# GigabitEthernet_VSC8211.net
KiCad netlist of a schematic drawn in Altium Designer
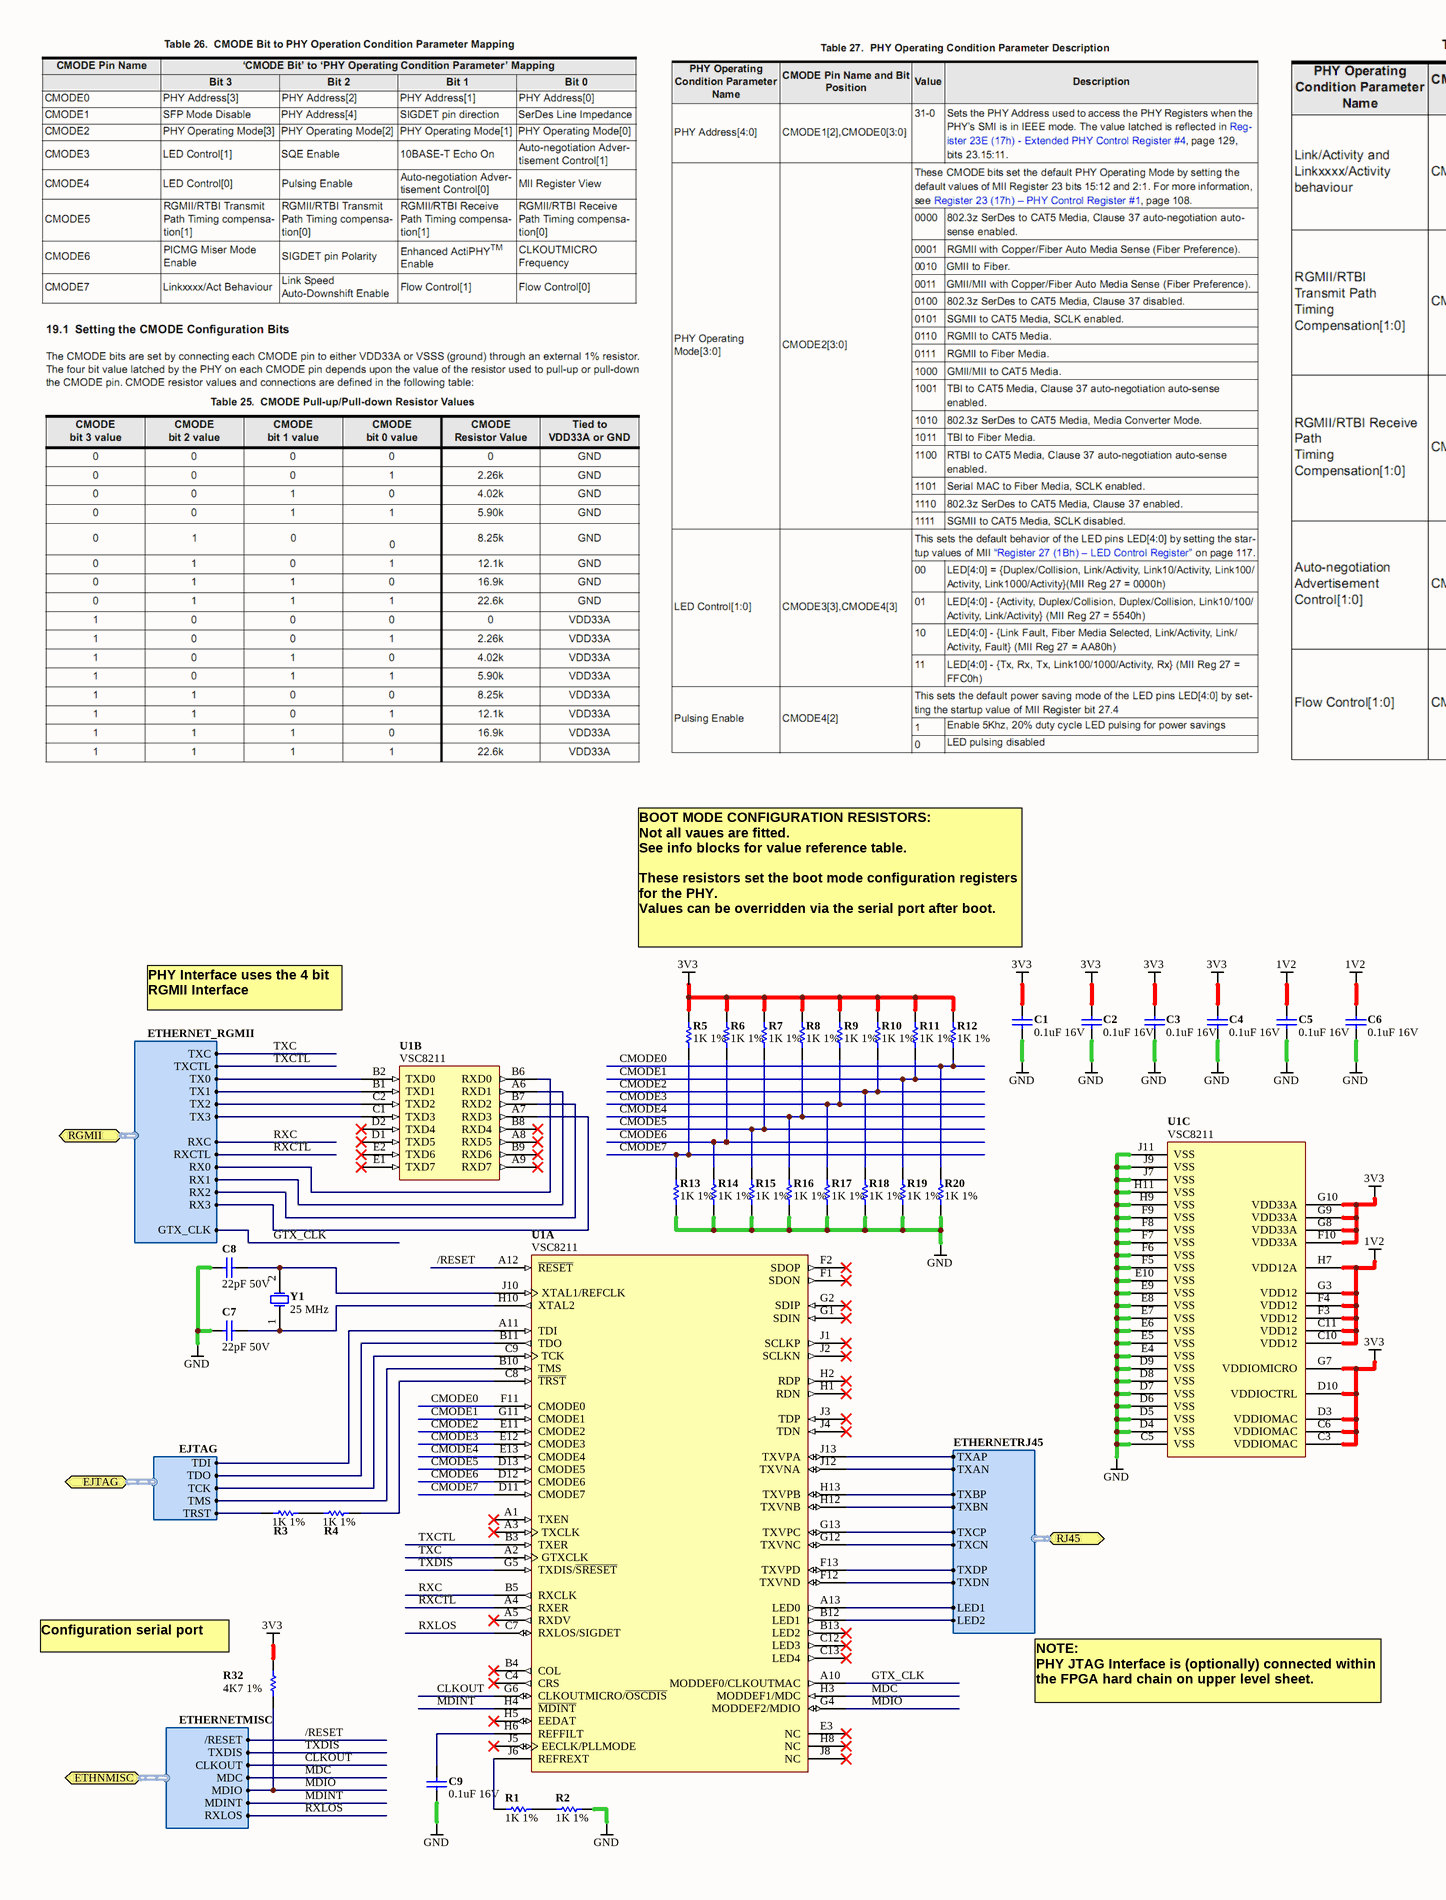
[diagram p0: GigabitEthernet_VSC8211.SchDoc, left]
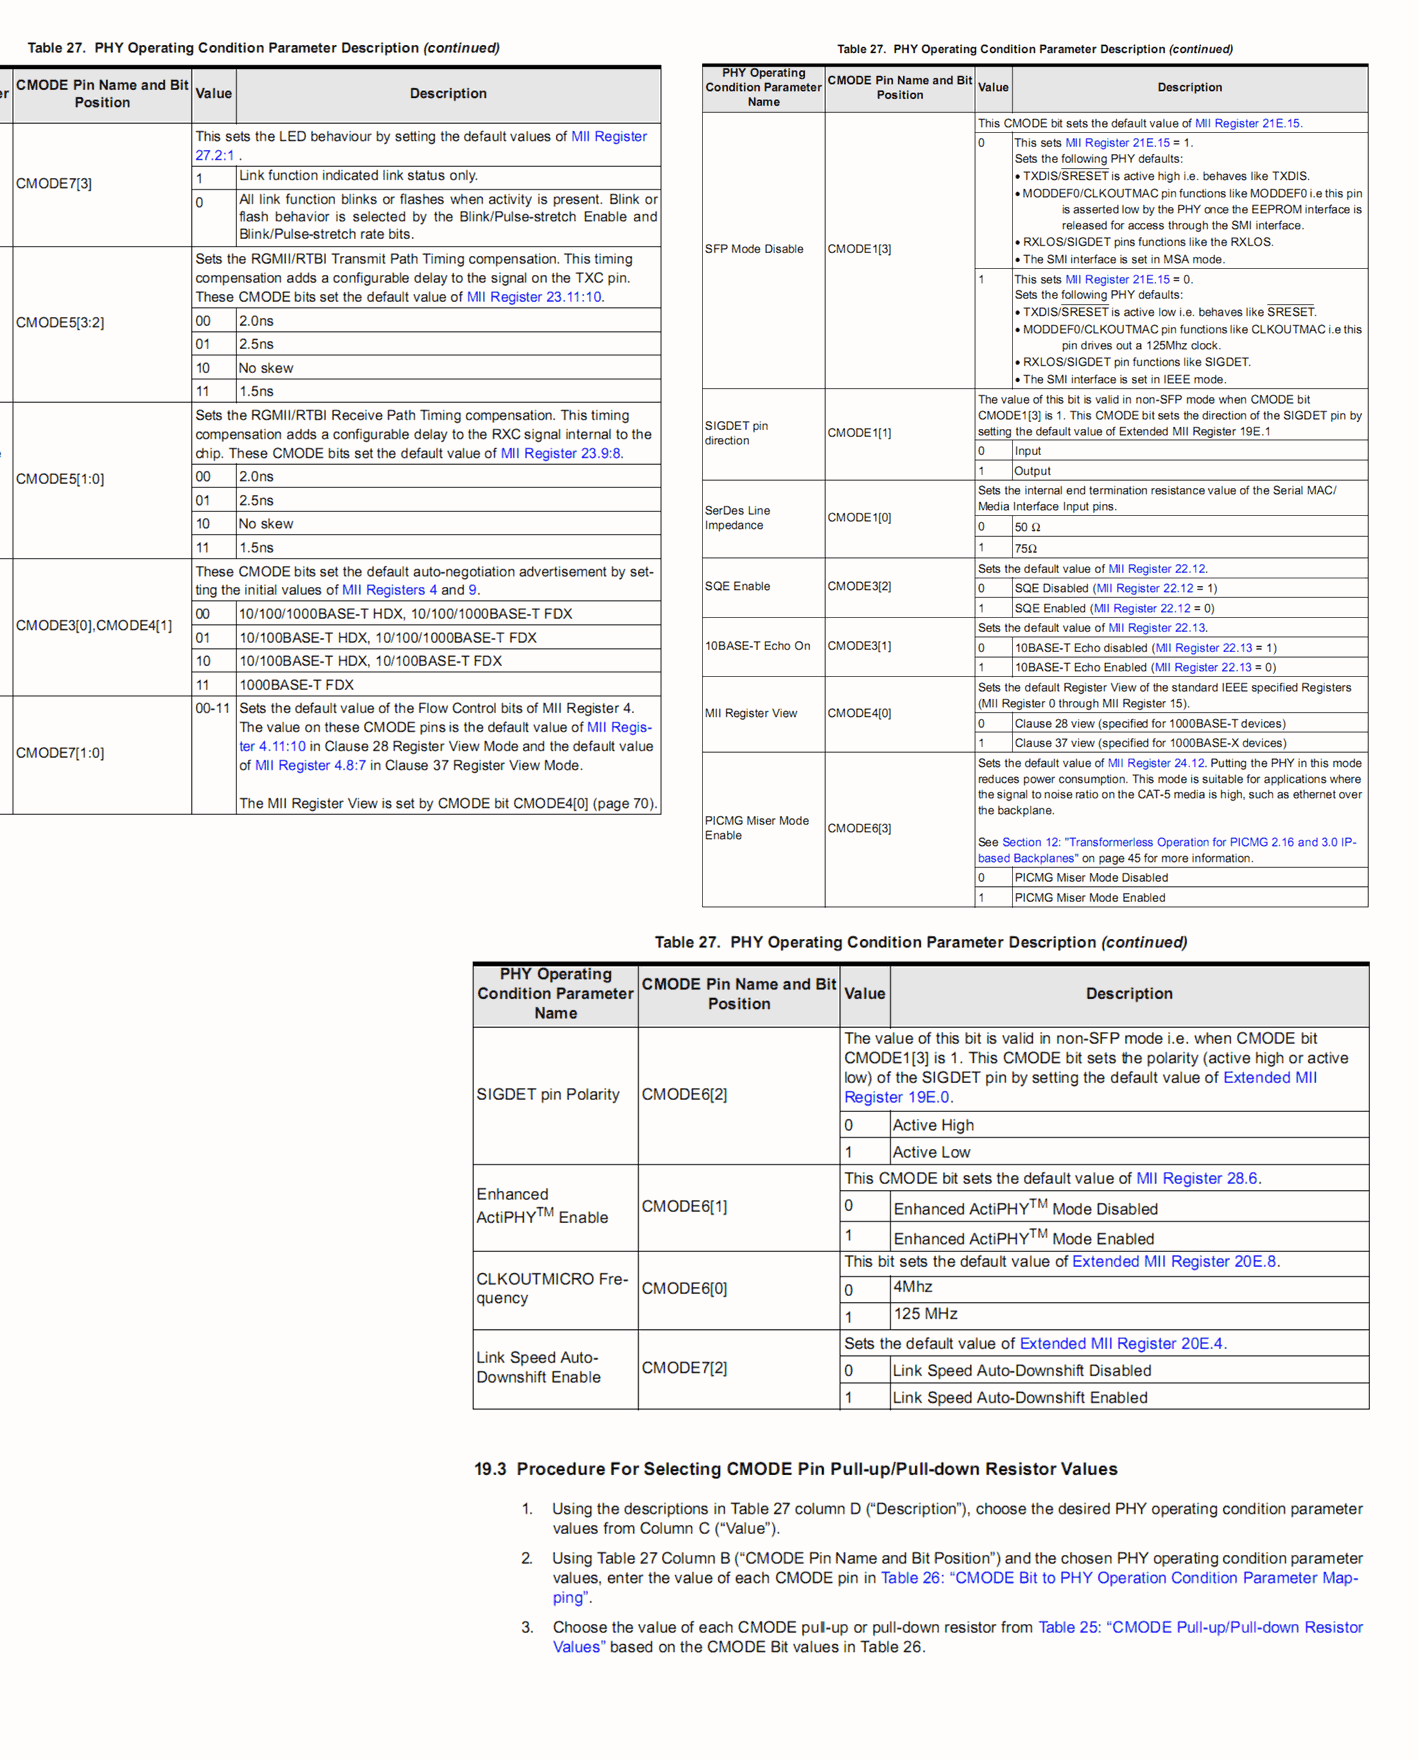
[diagram p1: GigabitEthernet_VSC8211.SchDoc, right]

(export (version "E")
  (design (tool "Eeschema 10.0.6"))
  (components
    (comp (ref "C1")
      (value "0.1uF 16V")
      (footprint "CAPC1005-STAR")
      (description "Capacitor, Ceramic, 0.1uF 10% 16V 0402 (1005) X7R")
      (fields (field (name "TOLERANCE") "10 %"))
      (libsource (lib "altium-import") (part "root_0_mirrored_CAP-NP_"))
    )
    (comp (ref "C2")
      (value "0.1uF 16V")
      (footprint "CAPC1005-STAR")
      (description "Capacitor, Ceramic, 0.1uF 10% 16V 0402 (1005) X7R")
      (fields (field (name "TOLERANCE") "10 %"))
      (libsource (lib "altium-import") (part "root_0_mirrored_CAP-NP_"))
    )
    (comp (ref "C3")
      (value "0.1uF 16V")
      (footprint "CAPC1005-STAR")
      (description "Capacitor, Ceramic, 0.1uF 10% 16V 0402 (1005) X7R")
      (fields (field (name "TOLERANCE") "10 %"))
      (libsource (lib "altium-import") (part "root_0_mirrored_CAP-NP_"))
    )
    (comp (ref "C4")
      (value "0.1uF 16V")
      (footprint "CAPC1005-STAR")
      (description "Capacitor, Ceramic, 0.1uF 10% 16V 0402 (1005) X7R")
      (fields (field (name "TOLERANCE") "10 %"))
      (libsource (lib "altium-import") (part "root_0_mirrored_CAP-NP_"))
    )
    (comp (ref "C5")
      (value "0.1uF 16V")
      (footprint "CAPC1005-STAR")
      (description "Capacitor, Ceramic, 0.1uF 10% 16V 0402 (1005) X7R")
      (fields (field (name "TOLERANCE") "10 %"))
      (libsource (lib "altium-import") (part "root_0_mirrored_CAP-NP_"))
    )
    (comp (ref "C6")
      (value "0.1uF 16V")
      (footprint "CAPC1005-STAR")
      (description "Capacitor, Ceramic, 0.1uF 10% 16V 0402 (1005) X7R")
      (fields (field (name "TOLERANCE") "10 %"))
      (libsource (lib "altium-import") (part "root_0_mirrored_CAP-NP_"))
    )
    (comp (ref "C7")
      (value "22pF 50V")
      (footprint "CAPC1005-STAR")
      (description "Capacitor, Ceramic, 22pF 5% 50V 0402 (1005) COG")
      (fields (field (name "TOLERANCE") "5 %"))
      (libsource (lib "AltiumDesignLibrary") (part "CAP-NP"))
    )
    (comp (ref "C8")
      (value "22pF 50V")
      (footprint "CAPC1005-STAR")
      (description "Capacitor, Ceramic, 22pF 5% 50V 0402 (1005) COG")
      (fields (field (name "TOLERANCE") "5 %"))
      (libsource (lib "AltiumDesignLibrary") (part "CAP-NP"))
    )
    (comp (ref "C9")
      (value "0.1uF 16V")
      (footprint "CAPC1005-STAR")
      (description "Capacitor, Ceramic, 0.1uF 10% 16V 0402 (1005) X7R")
      (fields (field (name "TOLERANCE") "10 %"))
      (libsource (lib "altium-import") (part "root_0_CAP-NP_"))
    )
    (comp (ref "R1")
      (value "1K 1%")
      (footprint "RESC1005-STAR")
      (description "Resistor, 1K 1% 0402 (1005)")
      (fields (field (name "TOLERANCE") "1 %"))
      (libsource (lib "AltiumDesignLibrary") (part "RES"))
    )
    (comp (ref "R2")
      (value "1K 1%")
      (footprint "RESC1005-STAR")
      (description "Resistor, 1K 1% 0402 (1005)")
      (fields (field (name "TOLERANCE") "1 %"))
      (libsource (lib "AltiumDesignLibrary") (part "RES"))
    )
    (comp (ref "R3")
      (value "1K 1%")
      (footprint "RESC1005-STAR")
      (description "Resistor, 1K 1% 0402 (1005)")
      (fields (field (name "TOLERANCE") "1 %"))
      (libsource (lib "AltiumDesignLibrary") (part "RES"))
    )
    (comp (ref "R4")
      (value "1K 1%")
      (footprint "RESC1005-STAR")
      (description "Resistor, 1K 1% 0402 (1005)")
      (fields (field (name "TOLERANCE") "1 %"))
      (libsource (lib "AltiumDesignLibrary") (part "RES"))
    )
    (comp (ref "R5")
      (value "1K 1%")
      (footprint "RESC1005-STAR")
      (description "Resistor, 1K 1% 0402 (1005)")
      (fields (field (name "TOLERANCE") "1 %"))
      (libsource (lib "AltiumDesignLibrary") (part "RES"))
    )
    (comp (ref "R6")
      (value "1K 1%")
      (footprint "RESC1005-STAR")
      (description "Resistor, 1K 1% 0402 (1005)")
      (fields (field (name "TOLERANCE") "1 %"))
      (libsource (lib "AltiumDesignLibrary") (part "RES"))
    )
    (comp (ref "R7")
      (value "1K 1%")
      (footprint "RESC1005-STAR")
      (description "Resistor, 1K 1% 0402 (1005)")
      (fields (field (name "TOLERANCE") "1 %"))
      (libsource (lib "AltiumDesignLibrary") (part "RES"))
    )
    (comp (ref "R8")
      (value "1K 1%")
      (footprint "RESC1005-STAR")
      (description "Resistor, 1K 1% 0402 (1005)")
      (fields (field (name "TOLERANCE") "1 %"))
      (libsource (lib "AltiumDesignLibrary") (part "RES"))
    )
    (comp (ref "R9")
      (value "1K 1%")
      (footprint "RESC1005-STAR")
      (description "Resistor, 1K 1% 0402 (1005)")
      (fields (field (name "TOLERANCE") "1 %"))
      (libsource (lib "AltiumDesignLibrary") (part "RES"))
    )
    (comp (ref "R10")
      (value "1K 1%")
      (footprint "RESC1005-STAR")
      (description "Resistor, 1K 1% 0402 (1005)")
      (fields (field (name "TOLERANCE") "1 %"))
      (libsource (lib "AltiumDesignLibrary") (part "RES"))
    )
    (comp (ref "R11")
      (value "1K 1%")
      (footprint "RESC1005-STAR")
      (description "Resistor, 1K 1% 0402 (1005)")
      (fields (field (name "TOLERANCE") "1 %"))
      (libsource (lib "AltiumDesignLibrary") (part "RES"))
    )
    (comp (ref "R12")
      (value "1K 1%")
      (footprint "RESC1005-STAR")
      (description "Resistor, 1K 1% 0402 (1005)")
      (fields (field (name "TOLERANCE") "1 %"))
      (libsource (lib "AltiumDesignLibrary") (part "RES"))
    )
    (comp (ref "R13")
      (value "1K 1%")
      (footprint "RESC1005-STAR")
      (description "Resistor, 1K 1% 0402 (1005)")
      (fields (field (name "TOLERANCE") "1 %"))
      (libsource (lib "AltiumDesignLibrary") (part "RES"))
    )
    (comp (ref "R14")
      (value "1K 1%")
      (footprint "RESC1005-STAR")
      (description "Resistor, 1K 1% 0402 (1005)")
      (fields (field (name "TOLERANCE") "1 %"))
      (libsource (lib "AltiumDesignLibrary") (part "RES"))
    )
    (comp (ref "R15")
      (value "1K 1%")
      (footprint "RESC1005-STAR")
      (description "Resistor, 1K 1% 0402 (1005)")
      (fields (field (name "TOLERANCE") "1 %"))
      (libsource (lib "AltiumDesignLibrary") (part "RES"))
    )
    (comp (ref "R16")
      (value "1K 1%")
      (footprint "RESC1005-STAR")
      (description "Resistor, 1K 1% 0402 (1005)")
      (fields (field (name "TOLERANCE") "1 %"))
      (libsource (lib "AltiumDesignLibrary") (part "RES"))
    )
    (comp (ref "R17")
      (value "1K 1%")
      (footprint "RESC1005-STAR")
      (description "Resistor, 1K 1% 0402 (1005)")
      (fields (field (name "TOLERANCE") "1 %"))
      (libsource (lib "AltiumDesignLibrary") (part "RES"))
    )
    (comp (ref "R18")
      (value "1K 1%")
      (footprint "RESC1005-STAR")
      (description "Resistor, 1K 1% 0402 (1005)")
      (fields (field (name "TOLERANCE") "1 %"))
      (libsource (lib "AltiumDesignLibrary") (part "RES"))
    )
    (comp (ref "R19")
      (value "1K 1%")
      (footprint "RESC1005-STAR")
      (description "Resistor, 1K 1% 0402 (1005)")
      (fields (field (name "TOLERANCE") "1 %"))
      (libsource (lib "AltiumDesignLibrary") (part "RES"))
    )
    (comp (ref "R20")
      (value "1K 1%")
      (footprint "RESC1005-STAR")
      (description "Resistor, 1K 1% 0402 (1005)")
      (fields (field (name "TOLERANCE") "1 %"))
      (libsource (lib "AltiumDesignLibrary") (part "RES"))
    )
    (comp (ref "R32")
      (value "4K7 1%")
      (footprint "RESC1005-STAR")
      (description "Resistor, 4K7 1% 0402 (1005)")
      (fields (field (name "TOLERANCE") "1 %"))
      (libsource (lib "AltiumDesignLibrary") (part "RES"))
    )
    (comp (ref "U1")
      (value "VSC8211")
      (footprint "BGA117C100P9X13_1000X1400X170")
      (description "Ethernet PHY, Gigabit, Vitesse, VSC8211")
      (libsource (lib "AltiumDesignLibrary") (part "VSC8211XVW"))
    )
    (comp (ref "Y1")
      (value "25 MHz")
      (footprint "XTAL_HC49SMD")
      (description "Crystal, 25 MHz  +/-30ppm 20pf HC49SMD")
      (libsource (lib "AltiumDesignLibrary") (part "CRYS"))
    )
  )
  (nets
    (net (code "5") (name "/CLKOUT") (class "Default")
      (node (ref "U1") (pin "G6") (pinfunction "CLKOUTMICRO/~{OSCDIS}_G6") (pintype "bidirectional"))
    )
    (net (code "6") (name "/CMODE0") (class "Default")
      (node (ref "R12") (pin "1") (pinfunction "1_1") (pintype "passive"))
      (node (ref "R20") (pin "2") (pinfunction "2_2") (pintype "passive"))
      (node (ref "U1") (pin "F11") (pinfunction "CMODE0_F11") (pintype "input"))
    )
    (net (code "7") (name "/CMODE1") (class "Default")
      (node (ref "R11") (pin "1") (pinfunction "1_1") (pintype "passive"))
      (node (ref "R19") (pin "2") (pinfunction "2_2") (pintype "passive"))
      (node (ref "U1") (pin "G11") (pinfunction "CMODE1_G11") (pintype "input"))
    )
    (net (code "8") (name "/CMODE2") (class "Default")
      (node (ref "R10") (pin "1") (pinfunction "1_1") (pintype "passive"))
      (node (ref "R18") (pin "2") (pinfunction "2_2") (pintype "passive"))
      (node (ref "U1") (pin "E11") (pinfunction "CMODE2_E11") (pintype "input"))
    )
    (net (code "9") (name "/CMODE3") (class "Default")
      (node (ref "R17") (pin "2") (pinfunction "2_2") (pintype "passive"))
      (node (ref "R9") (pin "1") (pinfunction "1_1") (pintype "passive"))
      (node (ref "U1") (pin "E12") (pinfunction "CMODE3_E12") (pintype "input"))
    )
    (net (code "10") (name "/CMODE4") (class "Default")
      (node (ref "R16") (pin "2") (pinfunction "2_2") (pintype "passive"))
      (node (ref "R8") (pin "1") (pinfunction "1_1") (pintype "passive"))
      (node (ref "U1") (pin "E13") (pinfunction "CMODE4_E13") (pintype "input"))
    )
    (net (code "11") (name "/CMODE5") (class "Default")
      (node (ref "R15") (pin "2") (pinfunction "2_2") (pintype "passive"))
      (node (ref "R7") (pin "1") (pinfunction "1_1") (pintype "passive"))
      (node (ref "U1") (pin "D13") (pinfunction "CMODE5_D13") (pintype "input"))
    )
    (net (code "12") (name "/CMODE6") (class "Default")
      (node (ref "R14") (pin "2") (pinfunction "2_2") (pintype "passive"))
      (node (ref "R6") (pin "1") (pinfunction "1_1") (pintype "passive"))
      (node (ref "U1") (pin "D12") (pinfunction "CMODE6_D12") (pintype "input"))
    )
    (net (code "13") (name "/CMODE7") (class "Default")
      (node (ref "R13") (pin "2") (pinfunction "2_2") (pintype "passive"))
      (node (ref "R5") (pin "1") (pinfunction "1_1") (pintype "passive"))
      (node (ref "U1") (pin "D11") (pinfunction "CMODE7_D11") (pintype "input"))
    )
    (net (code "14") (name "/GTX_CLK") (class "Default")
      (node (ref "U1") (pin "A10") (pinfunction "MODDEF0/CLKOUTMAC_A10") (pintype "output"))
    )
    (net (code "15") (name "/LED1") (class "Default")
      (node (ref "U1") (pin "A13") (pinfunction "LED0_A13") (pintype "output"))
    )
    (net (code "16") (name "/LED2") (class "Default")
      (node (ref "U1") (pin "B12") (pinfunction "LED1_B12") (pintype "output"))
    )
    (net (code "17") (name "/MDC") (class "Default")
      (node (ref "U1") (pin "H3") (pinfunction "MODDEF1/MDC_H3") (pintype "input"))
    )
    (net (code "18") (name "/MDINT") (class "Default")
      (node (ref "U1") (pin "H4") (pinfunction "~{MDINT}_H4") (pintype "open_collector"))
    )
    (net (code "19") (name "/MDIO") (class "Default")
      (node (ref "R32") (pin "1") (pinfunction "1_1") (pintype "passive"))
      (node (ref "U1") (pin "G4") (pinfunction "MODDEF2/MDIO_G4") (pintype "bidirectional"))
    )
    (net (code "20") (name "/RX0") (class "Default")
      (node (ref "U1") (pin "B6") (pinfunction "RXD0_B6") (pintype "output"))
    )
    (net (code "21") (name "/RX1") (class "Default")
      (node (ref "U1") (pin "A6") (pinfunction "RXD1_A6") (pintype "output"))
    )
    (net (code "22") (name "/RX2") (class "Default")
      (node (ref "U1") (pin "B7") (pinfunction "RXD2_B7") (pintype "output"))
    )
    (net (code "23") (name "/RX3") (class "Default")
      (node (ref "U1") (pin "A7") (pinfunction "RXD3_A7") (pintype "output"))
    )
    (net (code "24") (name "/RXC") (class "Default")
      (node (ref "U1") (pin "B5") (pinfunction "RXCLK_B5") (pintype "output"))
    )
    (net (code "25") (name "/RXCTL") (class "Default")
      (node (ref "U1") (pin "A4") (pinfunction "RXER_A4") (pintype "output"))
    )
    (net (code "26") (name "/RXLOS") (class "Default")
      (node (ref "U1") (pin "C7") (pinfunction "RXLOS/SIGDET_C7") (pintype "bidirectional"))
    )
    (net (code "27") (name "/TCK") (class "Default")
      (node (ref "U1") (pin "C9") (pinfunction "TCK_C9") (pintype "input"))
    )
    (net (code "28") (name "/TDI") (class "Default")
      (node (ref "U1") (pin "A11") (pinfunction "TDI_A11") (pintype "input"))
    )
    (net (code "29") (name "/TDO") (class "Default")
      (node (ref "U1") (pin "B11") (pinfunction "TDO_B11") (pintype "output"))
    )
    (net (code "30") (name "/TMS") (class "Default")
      (node (ref "U1") (pin "B10") (pinfunction "TMS_B10") (pintype "input"))
    )
    (net (code "31") (name "/TRST") (class "Default")
      (node (ref "R3") (pin "1") (pinfunction "1_1") (pintype "passive"))
    )
    (net (code "32") (name "/TX0") (class "Default")
      (node (ref "U1") (pin "B2") (pinfunction "TXD0_B2") (pintype "input"))
    )
    (net (code "33") (name "/TX1") (class "Default")
      (node (ref "U1") (pin "B1") (pinfunction "TXD1_B1") (pintype "input"))
    )
    (net (code "34") (name "/TX2") (class "Default")
      (node (ref "U1") (pin "C2") (pinfunction "TXD2_C2") (pintype "input"))
    )
    (net (code "35") (name "/TX3") (class "Default")
      (node (ref "U1") (pin "C1") (pinfunction "TXD3_C1") (pintype "input"))
    )
    (net (code "36") (name "/TXAN") (class "Default")
      (node (ref "U1") (pin "J12") (pinfunction "TXVNA_J12") (pintype "bidirectional"))
    )
    (net (code "37") (name "/TXAP") (class "Default")
      (node (ref "U1") (pin "J13") (pinfunction "TXVPA_J13") (pintype "bidirectional"))
    )
    (net (code "38") (name "/TXBN") (class "Default")
      (node (ref "U1") (pin "H12") (pinfunction "TXVNB_H12") (pintype "bidirectional"))
    )
    (net (code "39") (name "/TXBP") (class "Default")
      (node (ref "U1") (pin "H13") (pinfunction "TXVPB_H13") (pintype "bidirectional"))
    )
    (net (code "40") (name "/TXC") (class "Default")
      (node (ref "U1") (pin "A2") (pinfunction "GTXCLK_A2") (pintype "input"))
    )
    (net (code "41") (name "/TXCN") (class "Default")
      (node (ref "U1") (pin "G12") (pinfunction "TXVNC_G12") (pintype "bidirectional"))
    )
    (net (code "42") (name "/TXCP") (class "Default")
      (node (ref "U1") (pin "G13") (pinfunction "TXVPC_G13") (pintype "bidirectional"))
    )
    (net (code "43") (name "/TXCTL") (class "Default")
      (node (ref "U1") (pin "B3") (pinfunction "TXER_B3") (pintype "input"))
    )
    (net (code "44") (name "/TXDIS") (class "Default")
      (node (ref "U1") (pin "G5") (pinfunction "TXDIS/~{SRESET}_G5") (pintype "input"))
    )
    (net (code "45") (name "/TXDN") (class "Default")
      (node (ref "U1") (pin "F12") (pinfunction "TXVND_F12") (pintype "bidirectional"))
    )
    (net (code "46") (name "/TXDP") (class "Default")
      (node (ref "U1") (pin "F13") (pinfunction "TXVPD_F13") (pintype "bidirectional"))
    )
    (net (code "51") (name "/{slash}RESET") (class "Default")
      (node (ref "U1") (pin "A12") (pinfunction "~{RESET}_A12") (pintype "input"))
    )
    (net (code "52") (name "1V2") (class "Default")
      (node (ref "C5") (pin "1") (pinfunction "1_1") (pintype "passive"))
      (node (ref "C6") (pin "1") (pinfunction "1_1") (pintype "passive"))
      (node (ref "U1") (pin "C10") (pinfunction "VDD12_C10") (pintype "power_in"))
      (node (ref "U1") (pin "C11") (pinfunction "VDD12_C11") (pintype "power_in"))
      (node (ref "U1") (pin "F3") (pinfunction "VDD12_F3") (pintype "power_in"))
      (node (ref "U1") (pin "F4") (pinfunction "VDD12_F4") (pintype "power_in"))
      (node (ref "U1") (pin "G3") (pinfunction "VDD12_G3") (pintype "power_in"))
      (node (ref "U1") (pin "H7") (pinfunction "VDD12A_H7") (pintype "power_in"))
    )
    (net (code "53") (name "3V3") (class "Default")
      (node (ref "C1") (pin "1") (pinfunction "1_1") (pintype "passive"))
      (node (ref "C2") (pin "1") (pinfunction "1_1") (pintype "passive"))
      (node (ref "C3") (pin "1") (pinfunction "1_1") (pintype "passive"))
      (node (ref "C4") (pin "1") (pinfunction "1_1") (pintype "passive"))
      (node (ref "R10") (pin "2") (pinfunction "2_2") (pintype "passive"))
      (node (ref "R11") (pin "2") (pinfunction "2_2") (pintype "passive"))
      (node (ref "R12") (pin "2") (pinfunction "2_2") (pintype "passive"))
      (node (ref "R32") (pin "2") (pinfunction "2_2") (pintype "passive"))
      (node (ref "R5") (pin "2") (pinfunction "2_2") (pintype "passive"))
      (node (ref "R6") (pin "2") (pinfunction "2_2") (pintype "passive"))
      (node (ref "R7") (pin "2") (pinfunction "2_2") (pintype "passive"))
      (node (ref "R8") (pin "2") (pinfunction "2_2") (pintype "passive"))
      (node (ref "R9") (pin "2") (pinfunction "2_2") (pintype "passive"))
      (node (ref "U1") (pin "C3") (pinfunction "VDDIOMAC_C3") (pintype "power_in"))
      (node (ref "U1") (pin "C6") (pinfunction "VDDIOMAC_C6") (pintype "power_in"))
      (node (ref "U1") (pin "D10") (pinfunction "VDDIOCTRL_D10") (pintype "power_in"))
      (node (ref "U1") (pin "D3") (pinfunction "VDDIOMAC_D3") (pintype "power_in"))
      (node (ref "U1") (pin "F10") (pinfunction "VDD33A_F10") (pintype "power_in"))
      (node (ref "U1") (pin "G10") (pinfunction "VDD33A_G10") (pintype "power_in"))
      (node (ref "U1") (pin "G7") (pinfunction "VDDIOMICRO_G7") (pintype "power_in"))
      (node (ref "U1") (pin "G8") (pinfunction "VDD33A_G8") (pintype "power_in"))
      (node (ref "U1") (pin "G9") (pinfunction "VDD33A_G9") (pintype "power_in"))
    )
    (net (code "54") (name "GND") (class "Default")
      (node (ref "C1") (pin "2") (pinfunction "2_2") (pintype "passive"))
      (node (ref "C2") (pin "2") (pinfunction "2_2") (pintype "passive"))
      (node (ref "C3") (pin "2") (pinfunction "2_2") (pintype "passive"))
      (node (ref "C4") (pin "2") (pinfunction "2_2") (pintype "passive"))
      (node (ref "C5") (pin "2") (pinfunction "2_2") (pintype "passive"))
      (node (ref "C6") (pin "2") (pinfunction "2_2") (pintype "passive"))
      (node (ref "C7") (pin "2") (pinfunction "2_2") (pintype "passive"))
      (node (ref "C8") (pin "2") (pinfunction "2_2") (pintype "passive"))
      (node (ref "C9") (pin "2") (pinfunction "2_2") (pintype "passive"))
      (node (ref "R13") (pin "1") (pinfunction "1_1") (pintype "passive"))
      (node (ref "R14") (pin "1") (pinfunction "1_1") (pintype "passive"))
      (node (ref "R15") (pin "1") (pinfunction "1_1") (pintype "passive"))
      (node (ref "R16") (pin "1") (pinfunction "1_1") (pintype "passive"))
      (node (ref "R17") (pin "1") (pinfunction "1_1") (pintype "passive"))
      (node (ref "R18") (pin "1") (pinfunction "1_1") (pintype "passive"))
      (node (ref "R19") (pin "1") (pinfunction "1_1") (pintype "passive"))
      (node (ref "R2") (pin "2") (pinfunction "2_2") (pintype "passive"))
      (node (ref "R20") (pin "1") (pinfunction "1_1") (pintype "passive"))
      (node (ref "U1") (pin "C5") (pinfunction "VSS_C5") (pintype "power_in"))
      (node (ref "U1") (pin "D4") (pinfunction "VSS_D4") (pintype "power_in"))
      (node (ref "U1") (pin "D5") (pinfunction "VSS_D5") (pintype "power_in"))
      (node (ref "U1") (pin "D6") (pinfunction "VSS_D6") (pintype "power_in"))
      (node (ref "U1") (pin "D7") (pinfunction "VSS_D7") (pintype "power_in"))
      (node (ref "U1") (pin "D8") (pinfunction "VSS_D8") (pintype "power_in"))
      (node (ref "U1") (pin "D9") (pinfunction "VSS_D9") (pintype "power_in"))
      (node (ref "U1") (pin "E10") (pinfunction "VSS_E10") (pintype "power_in"))
      (node (ref "U1") (pin "E4") (pinfunction "VSS_E4") (pintype "power_in"))
      (node (ref "U1") (pin "E5") (pinfunction "VSS_E5") (pintype "power_in"))
      (node (ref "U1") (pin "E6") (pinfunction "VSS_E6") (pintype "power_in"))
      (node (ref "U1") (pin "E7") (pinfunction "VSS_E7") (pintype "power_in"))
      (node (ref "U1") (pin "E8") (pinfunction "VSS_E8") (pintype "power_in"))
      (node (ref "U1") (pin "E9") (pinfunction "VSS_E9") (pintype "power_in"))
      (node (ref "U1") (pin "F5") (pinfunction "VSS_F5") (pintype "power_in"))
      (node (ref "U1") (pin "F6") (pinfunction "VSS_F6") (pintype "power_in"))
      (node (ref "U1") (pin "F7") (pinfunction "VSS_F7") (pintype "power_in"))
      (node (ref "U1") (pin "F8") (pinfunction "VSS_F8") (pintype "power_in"))
      (node (ref "U1") (pin "F9") (pinfunction "VSS_F9") (pintype "power_in"))
      (node (ref "U1") (pin "H11") (pinfunction "VSS_H11") (pintype "power_in"))
      (node (ref "U1") (pin "H9") (pinfunction "VSS_H9") (pintype "power_in"))
      (node (ref "U1") (pin "J11") (pinfunction "VSS_J11") (pintype "power_in"))
      (node (ref "U1") (pin "J7") (pinfunction "VSS_J7") (pintype "power_in"))
      (node (ref "U1") (pin "J9") (pinfunction "VSS_J9") (pintype "power_in"))
    )
    (net (code "55") (name "Net-(R1-Pad2)") (class "Default")
      (node (ref "R1") (pin "2") (pinfunction "2_2") (pintype "passive"))
      (node (ref "R2") (pin "1") (pinfunction "1_1") (pintype "passive"))
    )
    (net (code "56") (name "Net-(R3-Pad2)") (class "Default")
      (node (ref "R3") (pin "2") (pinfunction "2_2") (pintype "passive"))
      (node (ref "R4") (pin "1") (pinfunction "1_1") (pintype "passive"))
    )
    (net (code "57") (name "Net-(U1A-REFFILT)") (class "Default")
      (node (ref "C9") (pin "1") (pinfunction "1_1") (pintype "passive"))
      (node (ref "U1") (pin "H6") (pinfunction "REFFILT_H6") (pintype "passive"))
    )
    (net (code "58") (name "Net-(U1A-REFREXT)") (class "Default")
      (node (ref "R1") (pin "1") (pinfunction "1_1") (pintype "passive"))
      (node (ref "U1") (pin "J6") (pinfunction "REFREXT_J6") (pintype "passive"))
    )
    (net (code "59") (name "Net-(U1A-XTAL1{slash}REFCLK)") (class "Default")
      (node (ref "C8") (pin "1") (pinfunction "1_1") (pintype "passive"))
      (node (ref "U1") (pin "J10") (pinfunction "XTAL1/REFCLK_J10") (pintype "input"))
      (node (ref "Y1") (pin "2") (pinfunction "OSC2_2") (pintype "passive"))
    )
    (net (code "60") (name "Net-(U1A-XTAL2)") (class "Default")
      (node (ref "C7") (pin "1") (pinfunction "1_1") (pintype "passive"))
      (node (ref "U1") (pin "H10") (pinfunction "XTAL2_H10") (pintype "output"))
      (node (ref "Y1") (pin "1") (pinfunction "OSC1_1") (pintype "passive"))
    )
    (net (code "61") (name "Net-(U1A-~{TRST})") (class "Default")
      (node (ref "R4") (pin "2") (pinfunction "2_2") (pintype "passive"))
      (node (ref "U1") (pin "C8") (pinfunction "~{TRST}_C8") (pintype "input"))
    )
    (net (code "62") (name "unconnected-(U1A-COL-PadB4)") (class "Default")
      (node (ref "U1") (pin "B4") (pinfunction "COL_B4") (pintype "output+no_connect"))
    )
    (net (code "63") (name "unconnected-(U1A-CRS-PadC4)") (class "Default")
      (node (ref "U1") (pin "C4") (pinfunction "CRS_C4") (pintype "output+no_connect"))
    )
    (net (code "64") (name "unconnected-(U1A-EECLK{slash}PLLMODE-PadJ5)") (class "Default")
      (node (ref "U1") (pin "J5") (pinfunction "EECLK/PLLMODE_J5") (pintype "bidirectional+no_connect"))
    )
    (net (code "65") (name "unconnected-(U1A-EEDAT-PadH5)") (class "Default")
      (node (ref "U1") (pin "H5") (pinfunction "EEDAT_H5") (pintype "bidirectional+no_connect"))
    )
    (net (code "66") (name "unconnected-(U1A-LED2-PadB13)") (class "Default")
      (node (ref "U1") (pin "B13") (pinfunction "LED2_B13") (pintype "output+no_connect"))
    )
    (net (code "67") (name "unconnected-(U1A-LED3-PadC12)") (class "Default")
      (node (ref "U1") (pin "C12") (pinfunction "LED3_C12") (pintype "output+no_connect"))
    )
    (net (code "68") (name "unconnected-(U1A-LED4-PadC13)") (class "Default")
      (node (ref "U1") (pin "C13") (pinfunction "LED4_C13") (pintype "output+no_connect"))
    )
    (net (code "69") (name "unconnected-(U1A-NC-PadE3)") (class "Default")
      (node (ref "U1") (pin "E3") (pinfunction "NC_E3") (pintype "passive+no_connect"))
    )
    (net (code "70") (name "unconnected-(U1A-NC-PadH8)") (class "Default")
      (node (ref "U1") (pin "H8") (pinfunction "NC_H8") (pintype "passive+no_connect"))
    )
    (net (code "71") (name "unconnected-(U1A-NC-PadJ8)") (class "Default")
      (node (ref "U1") (pin "J8") (pinfunction "NC_J8") (pintype "passive+no_connect"))
    )
    (net (code "72") (name "unconnected-(U1A-RDN-PadH1)") (class "Default")
      (node (ref "U1") (pin "H1") (pinfunction "RDN_H1") (pintype "output+no_connect"))
    )
    (net (code "73") (name "unconnected-(U1A-RDP-PadH2)") (class "Default")
      (node (ref "U1") (pin "H2") (pinfunction "RDP_H2") (pintype "output+no_connect"))
    )
    (net (code "74") (name "unconnected-(U1A-RXDV-PadA5)") (class "Default")
      (node (ref "U1") (pin "A5") (pinfunction "RXDV_A5") (pintype "output+no_connect"))
    )
    (net (code "75") (name "unconnected-(U1A-SCLKN-PadJ2)") (class "Default")
      (node (ref "U1") (pin "J2") (pinfunction "SCLKN_J2") (pintype "output+no_connect"))
    )
    (net (code "76") (name "unconnected-(U1A-SCLKP-PadJ1)") (class "Default")
      (node (ref "U1") (pin "J1") (pinfunction "SCLKP_J1") (pintype "output+no_connect"))
    )
    (net (code "77") (name "unconnected-(U1A-SDIN-PadG1)") (class "Default")
      (node (ref "U1") (pin "G1") (pinfunction "SDIN_G1") (pintype "input+no_connect"))
    )
    (net (code "78") (name "unconnected-(U1A-SDIP-PadG2)") (class "Default")
      (node (ref "U1") (pin "G2") (pinfunction "SDIP_G2") (pintype "input+no_connect"))
    )
    (net (code "79") (name "unconnected-(U1A-SDON-PadF1)") (class "Default")
      (node (ref "U1") (pin "F1") (pinfunction "SDON_F1") (pintype "output+no_connect"))
    )
    (net (code "80") (name "unconnected-(U1A-SDOP-PadF2)") (class "Default")
      (node (ref "U1") (pin "F2") (pinfunction "SDOP_F2") (pintype "output+no_connect"))
    )
    (net (code "81") (name "unconnected-(U1A-TDN-PadJ4)") (class "Default")
      (node (ref "U1") (pin "J4") (pinfunction "TDN_J4") (pintype "input+no_connect"))
    )
    (net (code "82") (name "unconnected-(U1A-TDP-PadJ3)") (class "Default")
      (node (ref "U1") (pin "J3") (pinfunction "TDP_J3") (pintype "input+no_connect"))
    )
    (net (code "83") (name "unconnected-(U1A-TXCLK-PadA3)") (class "Default")
      (node (ref "U1") (pin "A3") (pinfunction "TXCLK_A3") (pintype "input+no_connect"))
    )
    (net (code "84") (name "unconnected-(U1A-TXEN-PadA1)") (class "Default")
      (node (ref "U1") (pin "A1") (pinfunction "TXEN_A1") (pintype "input+no_connect"))
    )
    (net (code "85") (name "unconnected-(U1B-RXD4-PadB8)") (class "Default")
      (node (ref "U1") (pin "B8") (pinfunction "RXD4_B8") (pintype "output+no_connect"))
    )
    (net (code "86") (name "unconnected-(U1B-RXD5-PadA8)") (class "Default")
      (node (ref "U1") (pin "A8") (pinfunction "RXD5_A8") (pintype "output+no_connect"))
    )
    (net (code "87") (name "unconnected-(U1B-RXD6-PadB9)") (class "Default")
      (node (ref "U1") (pin "B9") (pinfunction "RXD6_B9") (pintype "output+no_connect"))
    )
    (net (code "88") (name "unconnected-(U1B-RXD7-PadA9)") (class "Default")
      (node (ref "U1") (pin "A9") (pinfunction "RXD7_A9") (pintype "output+no_connect"))
    )
    (net (code "89") (name "unconnected-(U1B-TXD4-PadD2)") (class "Default")
      (node (ref "U1") (pin "D2") (pinfunction "TXD4_D2") (pintype "input+no_connect"))
    )
    (net (code "90") (name "unconnected-(U1B-TXD5-PadD1)") (class "Default")
      (node (ref "U1") (pin "D1") (pinfunction "TXD5_D1") (pintype "input+no_connect"))
    )
    (net (code "91") (name "unconnected-(U1B-TXD6-PadE2)") (class "Default")
      (node (ref "U1") (pin "E2") (pinfunction "TXD6_E2") (pintype "input+no_connect"))
    )
    (net (code "92") (name "unconnected-(U1B-TXD7-PadE1)") (class "Default")
      (node (ref "U1") (pin "E1") (pinfunction "TXD7_E1") (pintype "input+no_connect"))
    )
  )
)
